# IC2.net
KiCad netlist of a schematic drawn in Altium Designer
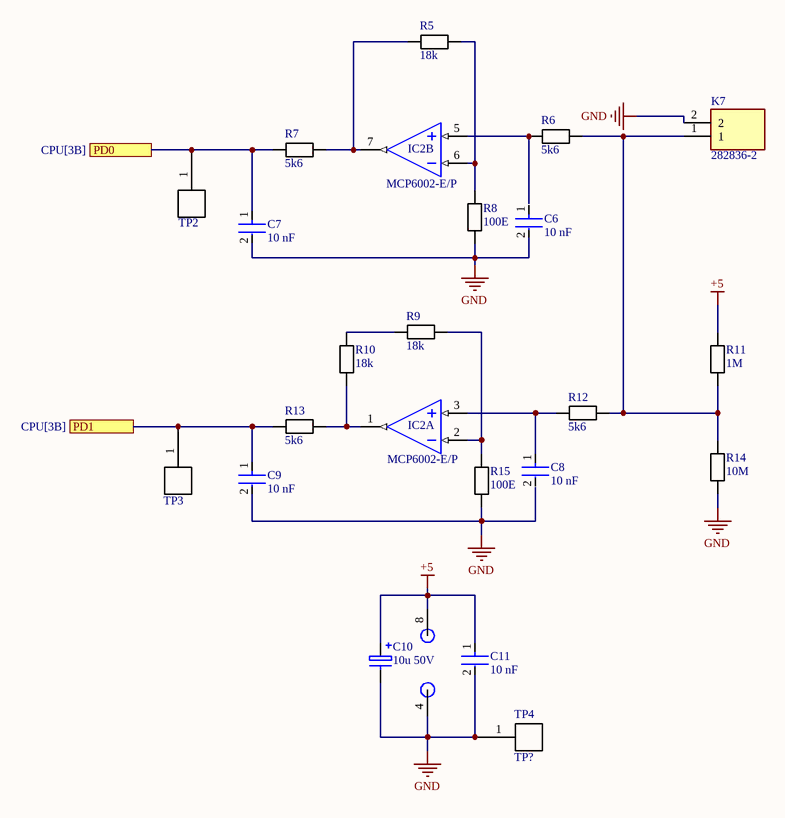
[diagram p0: IC2.SchDoc]

(export (version "E")
  (design (tool "Eeschema 10.0.6"))
  (components
    (comp (ref "C6")
      (value "10 nF")
      (footprint "0805")
      (description "Chip Multilayer Ceramic Capacitors for General Purpose, 0805, 10uF, X5R, 15%, 10%, 25V")
      (fields (field (name "VOLTAGE") "25V") (field (name "TOLERANCE") "10%"))
      (libsource (lib "soldeerstation") (part "Condensator 0805"))
    )
    (comp (ref "C7")
      (value "10 nF")
      (footprint "0805")
      (description "Chip Multilayer Ceramic Capacitors for General Purpose, 0805, 10uF, X5R, 15%, 10%, 25V")
      (fields (field (name "VOLTAGE") "25V") (field (name "TOLERANCE") "10%"))
      (libsource (lib "soldeerstation") (part "Condensator 0805"))
    )
    (comp (ref "C8")
      (value "10 nF")
      (footprint "0805")
      (description "Chip Multilayer Ceramic Capacitors for General Purpose, 0805, 10uF, X5R, 15%, 10%, 25V")
      (fields (field (name "VOLTAGE") "25V") (field (name "TOLERANCE") "10%"))
      (libsource (lib "soldeerstation") (part "Condensator 0805"))
    )
    (comp (ref "C9")
      (value "10 nF")
      (footprint "0805")
      (description "Chip Multilayer Ceramic Capacitors for General Purpose, 0805, 10uF, X5R, 15%, 10%, 25V")
      (fields (field (name "VOLTAGE") "25V") (field (name "TOLERANCE") "10%"))
      (libsource (lib "soldeerstation") (part "Condensator 0805"))
    )
    (comp (ref "C10")
      (value "10u 50V")
      (footprint "Elco 10uF 50V")
      (fields
        (field (name "PART NUMBER") "02015A270JAT2A")
        (field (name "MANUFACTURER") "AVX Interconnect / Elco")
      )
      (libsource (lib "soldeerstation") (part "Condensator Elco"))
    )
    (comp (ref "C11")
      (value "10 nF")
      (footprint "0805")
      (description "Chip Multilayer Ceramic Capacitors for General Purpose, 0805, 10uF, X5R, 15%, 10%, 25V")
      (fields (field (name "VOLTAGE") "25V") (field (name "TOLERANCE") "10%"))
      (libsource (lib "soldeerstation") (part "Condensator 0805"))
    )
    (comp (ref "IC2")
      (value "MCP6002-E/P")
      (footprint "MCP6002-E/P")
      (description "None")
      (libsource (lib "soldeerstation") (part "MCP6002-E/P"))
    )
    (comp (ref "K7")
      (value "282836-2")
      (footprint "Schroefconnector 2 Pin")
      (description "Connector")
      (libsource (lib "soldeerstation") (part "Schroefconnector 2 Pin L"))
    )
    (comp (ref "R5")
      (value "18k")
      (footprint "registor")
      (fields (field (name "MANUFACTURER") "Vishay Dale") (field (name "PART NUMBER") "CRCW08050000Z0EA"))
      (libsource (lib "Schlib1") (part "resistor"))
    )
    (comp (ref "R6")
      (value "5k6")
      (footprint "registor")
      (fields (field (name "MANUFACTURER") "Vishay Dale") (field (name "PART NUMBER") "CRCW08050000Z0EA"))
      (libsource (lib "Schlib1") (part "resistor"))
    )
    (comp (ref "R7")
      (value "5k6")
      (footprint "registor")
      (fields (field (name "MANUFACTURER") "Vishay Dale") (field (name "PART NUMBER") "CRCW08050000Z0EA"))
      (libsource (lib "Schlib1") (part "resistor"))
    )
    (comp (ref "R8")
      (value "100E")
      (footprint "registor")
      (fields (field (name "MANUFACTURER") "Vishay Dale") (field (name "PART NUMBER") "CRCW08050000Z0EA"))
      (libsource (lib "Schlib1") (part "resistor"))
    )
    (comp (ref "R9")
      (value "18k")
      (footprint "registor")
      (fields (field (name "MANUFACTURER") "Vishay Dale") (field (name "PART NUMBER") "CRCW08050000Z0EA"))
      (libsource (lib "Schlib1") (part "resistor"))
    )
    (comp (ref "R10")
      (value "18k")
      (footprint "registor")
      (fields (field (name "MANUFACTURER") "Vishay Dale") (field (name "PART NUMBER") "CRCW08050000Z0EA"))
      (libsource (lib "Schlib1") (part "resistor"))
    )
    (comp (ref "R11")
      (value "1M")
      (footprint "registor")
      (fields (field (name "MANUFACTURER") "Vishay Dale") (field (name "PART NUMBER") "CRCW08050000Z0EA"))
      (libsource (lib "Schlib1") (part "resistor"))
    )
    (comp (ref "R12")
      (value "5k6")
      (footprint "registor")
      (fields (field (name "MANUFACTURER") "Vishay Dale") (field (name "PART NUMBER") "CRCW08050000Z0EA"))
      (libsource (lib "Schlib1") (part "resistor"))
    )
    (comp (ref "R13")
      (value "5k6")
      (footprint "registor")
      (fields (field (name "MANUFACTURER") "Vishay Dale") (field (name "PART NUMBER") "CRCW08050000Z0EA"))
      (libsource (lib "Schlib1") (part "resistor"))
    )
    (comp (ref "R14")
      (value "10M")
      (footprint "registor")
      (fields (field (name "MANUFACTURER") "Vishay Dale") (field (name "PART NUMBER") "CRCW08050000Z0EA"))
      (libsource (lib "Schlib1") (part "resistor"))
    )
    (comp (ref "R15")
      (value "100E")
      (footprint "registor")
      (fields (field (name "MANUFACTURER") "Vishay Dale") (field (name "PART NUMBER") "CRCW08050000Z0EA"))
      (libsource (lib "Schlib1") (part "resistor"))
    )
    (comp (ref "TP2") (value "TP2") (footprint "testpunt") (libsource (lib "Schlib1") (part "testpunt")))
    (comp (ref "TP3") (value "TP?") (footprint "testpunt") (libsource (lib "Schlib1") (part "testpunt")))
    (comp (ref "TP4") (value "TP?") (footprint "testpunt") (libsource (lib "Schlib1") (part "testpunt")))
  )
  (nets
    (net (code "1") (name "+5") (class "Default")
      (node (ref "C10") (pin "1") (pinfunction "1_1") (pintype "passive"))
      (node (ref "C11") (pin "1") (pinfunction "1_1") (pintype "passive"))
      (node (ref "IC2") (pin "8") (pintype "passive"))
      (node (ref "R11") (pin "1") (pinfunction "1_1") (pintype "passive"))
    )
    (net (code "2") (name "/PD0") (class "Default")
      (node (ref "C7") (pin "1") (pinfunction "1_1") (pintype "passive"))
      (node (ref "R7") (pin "1") (pinfunction "1_1") (pintype "passive"))
      (node (ref "TP2") (pin "1") (pintype "passive"))
    )
    (net (code "3") (name "/PD1") (class "Default")
      (node (ref "C9") (pin "1") (pinfunction "1_1") (pintype "passive"))
      (node (ref "R13") (pin "1") (pinfunction "1_1") (pintype "passive"))
      (node (ref "TP3") (pin "1") (pintype "passive"))
    )
    (net (code "4") (name "GND") (class "Default")
      (node (ref "C10") (pin "2") (pinfunction "2_2") (pintype "passive"))
      (node (ref "C11") (pin "2") (pinfunction "2_2") (pintype "passive"))
      (node (ref "C6") (pin "2") (pinfunction "2_2") (pintype "passive"))
      (node (ref "C7") (pin "2") (pinfunction "2_2") (pintype "passive"))
      (node (ref "C9") (pin "2") (pinfunction "2_2") (pintype "passive"))
      (node (ref "IC2") (pin "4") (pintype "passive"))
      (node (ref "K7") (pin "2") (pinfunction "2_2") (pintype "passive"))
      (node (ref "R14") (pin "1") (pinfunction "1_1") (pintype "passive"))
      (node (ref "R15") (pin "1") (pinfunction "1_1") (pintype "passive"))
      (node (ref "R8") (pin "1") (pinfunction "1_1") (pintype "passive"))
      (node (ref "TP4") (pin "1") (pintype "passive"))
    )
    (net (code "5") (name "Net-(IC2A-VINA+)") (class "Default")
      (node (ref "C8") (pin "1") (pinfunction "1_1") (pintype "passive"))
      (node (ref "IC2") (pin "3") (pinfunction "VINA+_3") (pintype "input"))
      (node (ref "R12") (pin "1") (pinfunction "1_1") (pintype "passive"))
    )
    (net (code "6") (name "Net-(IC2A-VINA-)") (class "Default")
      (node (ref "IC2") (pin "2") (pinfunction "VINA-_2") (pintype "input"))
      (node (ref "R15") (pin "2") (pinfunction "2_2") (pintype "passive"))
      (node (ref "R9") (pin "1") (pinfunction "1_1") (pintype "passive"))
    )
    (net (code "7") (name "Net-(IC2A-VOUTA)") (class "Default")
      (node (ref "IC2") (pin "1") (pinfunction "VOUTA_1") (pintype "output"))
      (node (ref "R10") (pin "2") (pinfunction "2_2") (pintype "passive"))
      (node (ref "R13") (pin "2") (pinfunction "2_2") (pintype "passive"))
    )
    (net (code "8") (name "Net-(IC2B-VINB+)") (class "Default")
      (node (ref "IC2") (pin "5") (pinfunction "VINB+_5") (pintype "input"))
      (node (ref "R6") (pin "1") (pinfunction "1_1") (pintype "passive"))
    )
    (net (code "9") (name "Net-(IC2B-VINB-)") (class "Default")
      (node (ref "IC2") (pin "6") (pinfunction "VINB-_6") (pintype "input"))
      (node (ref "R5") (pin "2") (pinfunction "2_2") (pintype "passive"))
      (node (ref "R8") (pin "2") (pinfunction "2_2") (pintype "passive"))
    )
    (net (code "10") (name "Net-(IC2B-VOUTB)") (class "Default")
      (node (ref "IC2") (pin "7") (pinfunction "VOUTB_7") (pintype "output"))
      (node (ref "R5") (pin "1") (pinfunction "1_1") (pintype "passive"))
      (node (ref "R7") (pin "2") (pinfunction "2_2") (pintype "passive"))
    )
    (net (code "11") (name "Net-(K7-Pad1)") (class "Default")
      (node (ref "K7") (pin "1") (pinfunction "1_1") (pintype "passive"))
      (node (ref "R11") (pin "2") (pinfunction "2_2") (pintype "passive"))
      (node (ref "R12") (pin "2") (pinfunction "2_2") (pintype "passive"))
      (node (ref "R14") (pin "2") (pinfunction "2_2") (pintype "passive"))
      (node (ref "R6") (pin "2") (pinfunction "2_2") (pintype "passive"))
    )
    (net (code "12") (name "Net-(R10-Pad1)") (class "Default")
      (node (ref "R10") (pin "1") (pinfunction "1_1") (pintype "passive"))
      (node (ref "R9") (pin "2") (pinfunction "2_2") (pintype "passive"))
    )
    (net (code "13") (name "unconnected-(C6-Pad1)") (class "Default")
      (node (ref "C6") (pin "1") (pinfunction "1_1") (pintype "passive"))
    )
    (net (code "14") (name "unconnected-(C8-Pad2)") (class "Default")
      (node (ref "C8") (pin "2") (pinfunction "2_2") (pintype "passive"))
    )
  )
)
